# ethernet.net
KiCad netlist of a schematic drawn in Altium Designer
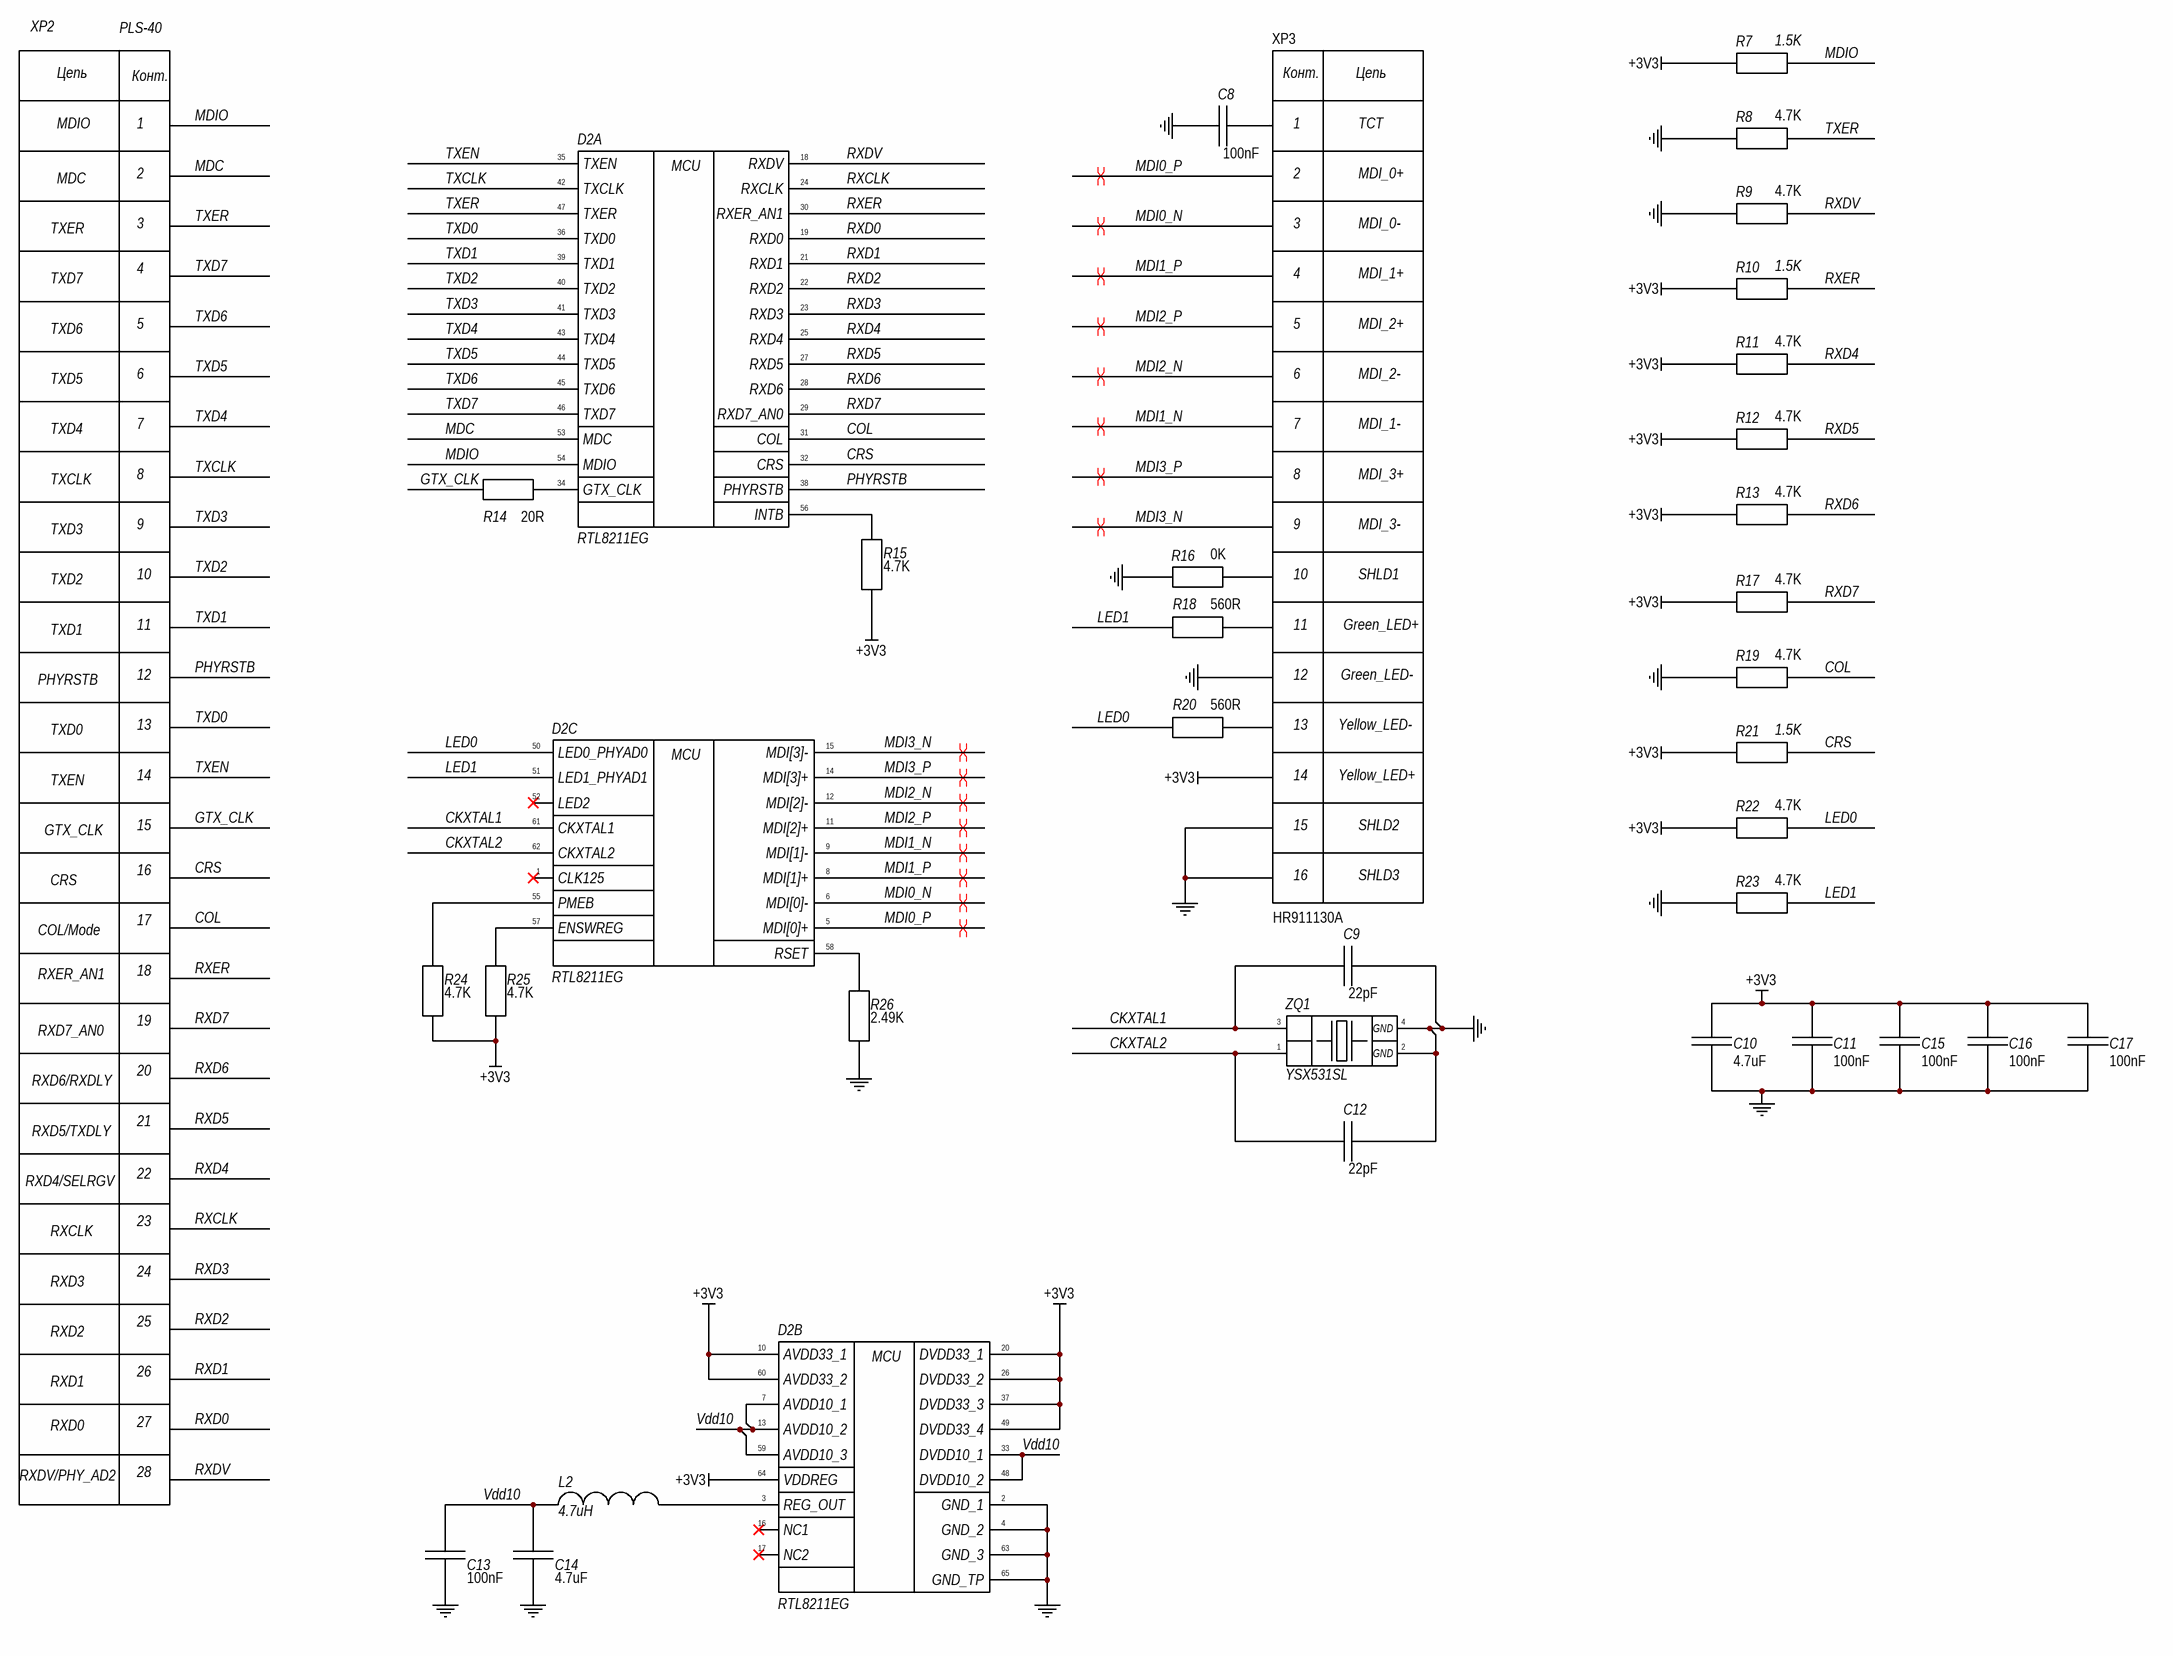
[diagram p0: ethernet.SchDoc]

(export (version "E")
  (design (tool "Eeschema 10.0.6"))
  (components
    (comp (ref "C8")
      (value "100nF")
      (footprint "SMD 0805")
      (description "Конденсатор номиналом 1.5 nF")
      (libsource (lib "Capacitors") (part "100nF"))
    )
    (comp (ref "C9")
      (value "22pF")
      (footprint "SMD 0805")
      (description "Конденсатор номиналом 22 pF")
      (libsource (lib "Capacitors") (part "22pF"))
    )
    (comp (ref "C10")
      (value "4.7uF")
      (footprint "SMD 0805")
      (description "Конденсатор номиналом 4.7 uF")
      (libsource (lib "Capacitors") (part "4.7uF"))
    )
    (comp (ref "C11")
      (value "100nF")
      (footprint "SMD 0805")
      (description "Конденсатор номиналом 1.5 nF")
      (libsource (lib "Capacitors") (part "100nF"))
    )
    (comp (ref "C12")
      (value "22pF")
      (footprint "SMD 0805")
      (description "Конденсатор номиналом 22 pF")
      (libsource (lib "Capacitors") (part "22pF"))
    )
    (comp (ref "C13")
      (value "100nF")
      (footprint "SMD 0805")
      (description "Конденсатор номиналом 1.5 nF")
      (libsource (lib "Capacitors") (part "100nF"))
    )
    (comp (ref "C14")
      (value "4.7uF")
      (footprint "SMD 0805")
      (description "Конденсатор номиналом 4.7 uF")
      (libsource (lib "Capacitors") (part "4.7uF"))
    )
    (comp (ref "C15")
      (value "100nF")
      (footprint "SMD 0805")
      (description "Конденсатор номиналом 1.5 nF")
      (libsource (lib "Capacitors") (part "100nF"))
    )
    (comp (ref "C16")
      (value "100nF")
      (footprint "SMD 0805")
      (description "Конденсатор номиналом 1.5 nF")
      (libsource (lib "Capacitors") (part "100nF"))
    )
    (comp (ref "C17")
      (value "100nF")
      (footprint "SMD 0805")
      (description "Конденсатор номиналом 1.5 nF")
      (libsource (lib "Capacitors") (part "100nF"))
    )
    (comp (ref "D2")
      (value "RTL8211EG")
      (footprint "Logic:QFN50P900X900X100_HS-65N")
      (libsource (lib "Logic") (part "RTL8211EG"))
    )
    (comp (ref "L2")
      (value "4.7uH")
      (footprint "SP43-4R7M")
      (description "Катушка индуктивности 4.7 мкГн")
      (libsource (lib "Inductors & Transformers") (part "4.7u"))
    )
    (comp (ref "R7")
      (value "1.5K")
      (footprint "RESC0805")
      (description "Резистор номиналом 1.5 кОм")
      (libsource (lib "Resistors") (part "1.5K"))
    )
    (comp (ref "R8")
      (value "4.7K")
      (footprint "RESC0805")
      (description "Резистор номиналом 4.7 кОм")
      (libsource (lib "Resistors") (part "4.7K"))
    )
    (comp (ref "R9")
      (value "4.7K")
      (footprint "RESC0805")
      (description "Резистор номиналом 4.7 кОм")
      (libsource (lib "Resistors") (part "4.7K"))
    )
    (comp (ref "R10")
      (value "1.5K")
      (footprint "RESC0805")
      (description "Резистор номиналом 1.5 кОм")
      (libsource (lib "Resistors") (part "1.5K"))
    )
    (comp (ref "R11")
      (value "4.7K")
      (footprint "RESC0805")
      (description "Резистор номиналом 4.7 кОм")
      (libsource (lib "Resistors") (part "4.7K"))
    )
    (comp (ref "R12")
      (value "4.7K")
      (footprint "RESC0805")
      (description "Резистор номиналом 4.7 кОм")
      (libsource (lib "Resistors") (part "4.7K"))
    )
    (comp (ref "R13")
      (value "4.7K")
      (footprint "RESC0805")
      (description "Резистор номиналом 4.7 кОм")
      (libsource (lib "Resistors") (part "4.7K"))
    )
    (comp (ref "R14")
      (value "20R")
      (footprint "RESC0805")
      (description "Резистор номиналом 20 Ом")
      (libsource (lib "Resistors") (part "20R"))
    )
    (comp (ref "R15")
      (value "4.7K")
      (footprint "RESC0805")
      (description "Резистор номиналом 4.7 кОм")
      (libsource (lib "Resistors") (part "4.7K"))
    )
    (comp (ref "R16")
      (value "0K")
      (footprint "RESC0805")
      (description "Резистор номиналом 0 Ом")
      (libsource (lib "Resistors") (part "0K"))
    )
    (comp (ref "R17")
      (value "4.7K")
      (footprint "RESC0805")
      (description "Резистор номиналом 4.7 кОм")
      (libsource (lib "Resistors") (part "4.7K"))
    )
    (comp (ref "R18")
      (value "560R")
      (footprint "RESC0805")
      (description "Резистор номиналом 560 Ом")
      (libsource (lib "Resistors") (part "560R"))
    )
    (comp (ref "R19")
      (value "4.7K")
      (footprint "RESC0805")
      (description "Резистор номиналом 4.7 кОм")
      (libsource (lib "Resistors") (part "4.7K"))
    )
    (comp (ref "R20")
      (value "560R")
      (footprint "RESC0805")
      (description "Резистор номиналом 560 Ом")
      (libsource (lib "Resistors") (part "560R"))
    )
    (comp (ref "R21")
      (value "1.5K")
      (footprint "RESC0805")
      (description "Резистор номиналом 1.5 кОм")
      (libsource (lib "Resistors") (part "1.5K"))
    )
    (comp (ref "R22")
      (value "4.7K")
      (footprint "RESC0805")
      (description "Резистор номиналом 4.7 кОм")
      (libsource (lib "Resistors") (part "4.7K"))
    )
    (comp (ref "R23")
      (value "4.7K")
      (footprint "RESC0805")
      (description "Резистор номиналом 4.7 кОм")
      (libsource (lib "Resistors") (part "4.7K"))
    )
    (comp (ref "R24")
      (value "4.7K")
      (footprint "RESC0805")
      (description "Резистор номиналом 4.7 кОм")
      (libsource (lib "Resistors") (part "4.7K"))
    )
    (comp (ref "R25")
      (value "4.7K")
      (footprint "RESC0805")
      (description "Резистор номиналом 4.7 кОм")
      (libsource (lib "Resistors") (part "4.7K"))
    )
    (comp (ref "R26")
      (value "2.49K")
      (footprint "RESC0805")
      (description "Резистор номиналом 2.49 кОм")
      (libsource (lib "Resistors") (part "2.49K"))
    )
    (comp (ref "XP2")
      (value "PLS-40")
      (footprint "PBD-28")
      (description "Служит для подключения разрабатываемой платы")
      (libsource (lib "Connectors") (part "SMT_FPGA"))
    )
    (comp (ref "XP3")
      (value "HR911130A")
      (footprint "Connectors:HR911130A")
      (description "Разъём RJ45 с встроенными трансформаторами и индикацией, 10/100Base-T Ethernet (HR911130A)")
      (libsource (lib "Connectors") (part "RJ-45"))
    )
    (comp (ref "ZQ1")
      (value "YSX531SL")
      (footprint "YSX531SL")
      (description "Кварцевый резонатор")
      (libsource (lib "Crystals & Oscillators") (part "YSX531SL"))
    )
  )
  (nets
    (net (code "1") (name "+3V3") (class "Default")
      (node (ref "C10") (pin "2") (pinfunction "2_2") (pintype "passive"))
      (node (ref "C11") (pin "2") (pinfunction "2_2") (pintype "passive"))
      (node (ref "C15") (pin "2") (pinfunction "2_2") (pintype "passive"))
      (node (ref "C16") (pin "2") (pinfunction "2_2") (pintype "passive"))
      (node (ref "C17") (pin "2") (pinfunction "2_2") (pintype "passive"))
      (node (ref "D2") (pin "10") (pinfunction "AVDD33_1_10") (pintype "passive"))
      (node (ref "D2") (pin "20") (pinfunction "DVDD33_1_20") (pintype "passive"))
      (node (ref "D2") (pin "26") (pinfunction "DVDD33_2_26") (pintype "passive"))
      (node (ref "D2") (pin "37") (pinfunction "DVDD33_3_37") (pintype "passive"))
      (node (ref "D2") (pin "49") (pinfunction "DVDD33_4_49") (pintype "passive"))
      (node (ref "D2") (pin "60") (pinfunction "AVDD33_2_60") (pintype "passive"))
      (node (ref "D2") (pin "64") (pinfunction "VDDREG_64") (pintype "passive"))
      (node (ref "R10") (pin "1") (pinfunction "1_1") (pintype "passive"))
      (node (ref "R11") (pin "1") (pinfunction "1_1") (pintype "passive"))
      (node (ref "R12") (pin "1") (pinfunction "1_1") (pintype "passive"))
      (node (ref "R13") (pin "1") (pinfunction "1_1") (pintype "passive"))
      (node (ref "R15") (pin "1") (pinfunction "1_1") (pintype "passive"))
      (node (ref "R17") (pin "1") (pinfunction "1_1") (pintype "passive"))
      (node (ref "R21") (pin "1") (pinfunction "1_1") (pintype "passive"))
      (node (ref "R22") (pin "1") (pinfunction "1_1") (pintype "passive"))
      (node (ref "R24") (pin "1") (pinfunction "1_1") (pintype "passive"))
      (node (ref "R25") (pin "1") (pinfunction "1_1") (pintype "passive"))
      (node (ref "R7") (pin "1") (pinfunction "1_1") (pintype "passive"))
      (node (ref "XP3") (pin "14") (pinfunction "14_14") (pintype "passive"))
    )
    (net (code "2") (name "/CKXTAL1") (class "Default")
      (node (ref "C9") (pin "1") (pinfunction "1_1") (pintype "passive"))
      (node (ref "D2") (pin "61") (pinfunction "CKXTAL1_61") (pintype "passive"))
      (node (ref "ZQ1") (pin "3") (pinfunction "3_3") (pintype "passive"))
    )
    (net (code "3") (name "/CKXTAL2") (class "Default")
      (node (ref "C12") (pin "1") (pinfunction "1_1") (pintype "passive"))
      (node (ref "D2") (pin "62") (pinfunction "CKXTAL2_62") (pintype "passive"))
      (node (ref "ZQ1") (pin "1") (pinfunction "1_1") (pintype "passive"))
    )
    (net (code "4") (name "/COL") (class "Default")
      (node (ref "D2") (pin "31") (pinfunction "COL_31") (pintype "passive"))
      (node (ref "R19") (pin "2") (pinfunction "2_2") (pintype "passive"))
      (node (ref "XP2") (pin "17") (pinfunction "17_17") (pintype "passive"))
    )
    (net (code "5") (name "/CRS") (class "Default")
      (node (ref "D2") (pin "32") (pinfunction "CRS_32") (pintype "passive"))
      (node (ref "R21") (pin "2") (pinfunction "2_2") (pintype "passive"))
      (node (ref "XP2") (pin "16") (pinfunction "16_16") (pintype "passive"))
    )
    (net (code "6") (name "/GTX_CLK") (class "Default")
      (node (ref "R14") (pin "1") (pinfunction "1_1") (pintype "passive"))
      (node (ref "XP2") (pin "15") (pinfunction "15_15") (pintype "passive"))
    )
    (net (code "7") (name "/LED0") (class "Default")
      (node (ref "D2") (pin "50") (pinfunction "LED0_PHYAD0_50") (pintype "passive"))
      (node (ref "R20") (pin "1") (pinfunction "1_1") (pintype "passive"))
      (node (ref "R22") (pin "2") (pinfunction "2_2") (pintype "passive"))
    )
    (net (code "8") (name "/LED1") (class "Default")
      (node (ref "D2") (pin "51") (pinfunction "LED1_PHYAD1_51") (pintype "passive"))
      (node (ref "R18") (pin "1") (pinfunction "1_1") (pintype "passive"))
      (node (ref "R23") (pin "2") (pinfunction "2_2") (pintype "passive"))
    )
    (net (code "9") (name "/MDC") (class "Default")
      (node (ref "D2") (pin "53") (pinfunction "MDC_53") (pintype "passive"))
      (node (ref "XP2") (pin "2") (pinfunction "2_2") (pintype "passive"))
    )
    (net (code "10") (name "/MDI0_N") (class "Default")
      (node (ref "D2") (pin "6") (pinfunction "MDI[0]-_6") (pintype "passive"))
      (node (ref "XP3") (pin "3") (pinfunction "3_3") (pintype "passive"))
    )
    (net (code "11") (name "/MDI0_P") (class "Default")
      (node (ref "D2") (pin "5") (pinfunction "MDI[0]+_5") (pintype "passive"))
      (node (ref "XP3") (pin "2") (pinfunction "2_2") (pintype "passive"))
    )
    (net (code "12") (name "/MDI1_N") (class "Default")
      (node (ref "D2") (pin "9") (pinfunction "MDI[1]-_9") (pintype "passive"))
      (node (ref "XP3") (pin "7") (pinfunction "7_7") (pintype "passive"))
    )
    (net (code "13") (name "/MDI1_P") (class "Default")
      (node (ref "D2") (pin "8") (pinfunction "MDI[1]+_8") (pintype "passive"))
      (node (ref "XP3") (pin "4") (pinfunction "4_4") (pintype "passive"))
    )
    (net (code "14") (name "/MDI2_N") (class "Default")
      (node (ref "D2") (pin "12") (pinfunction "MDI[2]-_12") (pintype "passive"))
      (node (ref "XP3") (pin "6") (pinfunction "6_6") (pintype "passive"))
    )
    (net (code "15") (name "/MDI2_P") (class "Default")
      (node (ref "D2") (pin "11") (pinfunction "MDI[2]+_11") (pintype "passive"))
      (node (ref "XP3") (pin "5") (pinfunction "5_5") (pintype "passive"))
    )
    (net (code "16") (name "/MDI3_N") (class "Default")
      (node (ref "D2") (pin "15") (pinfunction "MDI[3]-_15") (pintype "passive"))
      (node (ref "XP3") (pin "9") (pinfunction "9_9") (pintype "passive"))
    )
    (net (code "17") (name "/MDI3_P") (class "Default")
      (node (ref "D2") (pin "14") (pinfunction "MDI[3]+_14") (pintype "passive"))
      (node (ref "XP3") (pin "8") (pinfunction "8_8") (pintype "passive"))
    )
    (net (code "18") (name "/MDIO") (class "Default")
      (node (ref "D2") (pin "54") (pinfunction "MDIO_54") (pintype "passive"))
      (node (ref "R7") (pin "2") (pinfunction "2_2") (pintype "passive"))
      (node (ref "XP2") (pin "1") (pinfunction "1_1") (pintype "passive"))
    )
    (net (code "19") (name "/PHYRSTB") (class "Default")
      (node (ref "D2") (pin "38") (pinfunction "PHYRSTB_38") (pintype "passive"))
      (node (ref "XP2") (pin "12") (pinfunction "12_12") (pintype "passive"))
    )
    (net (code "20") (name "/RXCLK") (class "Default")
      (node (ref "D2") (pin "24") (pinfunction "RXCLK_24") (pintype "passive"))
      (node (ref "XP2") (pin "23") (pinfunction "23_23") (pintype "passive"))
    )
    (net (code "21") (name "/RXD0") (class "Default")
      (node (ref "D2") (pin "19") (pinfunction "RXD0_19") (pintype "passive"))
      (node (ref "XP2") (pin "27") (pinfunction "27_27") (pintype "passive"))
    )
    (net (code "22") (name "/RXD1") (class "Default")
      (node (ref "D2") (pin "21") (pinfunction "RXD1_21") (pintype "passive"))
      (node (ref "XP2") (pin "26") (pinfunction "26_26") (pintype "passive"))
    )
    (net (code "23") (name "/RXD2") (class "Default")
      (node (ref "D2") (pin "22") (pinfunction "RXD2_22") (pintype "passive"))
      (node (ref "XP2") (pin "25") (pinfunction "25_25") (pintype "passive"))
    )
    (net (code "24") (name "/RXD3") (class "Default")
      (node (ref "D2") (pin "23") (pinfunction "RXD3_23") (pintype "passive"))
      (node (ref "XP2") (pin "24") (pinfunction "24_24") (pintype "passive"))
    )
    (net (code "25") (name "/RXD4") (class "Default")
      (node (ref "D2") (pin "25") (pinfunction "RXD4_25") (pintype "passive"))
      (node (ref "R11") (pin "2") (pinfunction "2_2") (pintype "passive"))
      (node (ref "XP2") (pin "22") (pinfunction "22_22") (pintype "passive"))
    )
    (net (code "26") (name "/RXD5") (class "Default")
      (node (ref "D2") (pin "27") (pinfunction "RXD5_27") (pintype "passive"))
      (node (ref "R12") (pin "2") (pinfunction "2_2") (pintype "passive"))
      (node (ref "XP2") (pin "21") (pinfunction "21_21") (pintype "passive"))
    )
    (net (code "27") (name "/RXD6") (class "Default")
      (node (ref "D2") (pin "28") (pinfunction "RXD6_28") (pintype "passive"))
      (node (ref "R13") (pin "2") (pinfunction "2_2") (pintype "passive"))
      (node (ref "XP2") (pin "20") (pinfunction "20_20") (pintype "passive"))
    )
    (net (code "28") (name "/RXD7") (class "Default")
      (node (ref "D2") (pin "29") (pinfunction "RXD7_AN0_29") (pintype "passive"))
      (node (ref "R17") (pin "2") (pinfunction "2_2") (pintype "passive"))
      (node (ref "XP2") (pin "19") (pinfunction "19_19") (pintype "passive"))
    )
    (net (code "29") (name "/RXDV") (class "Default")
      (node (ref "D2") (pin "18") (pinfunction "RXDV_18") (pintype "passive"))
      (node (ref "R9") (pin "2") (pinfunction "2_2") (pintype "passive"))
      (node (ref "XP2") (pin "28") (pinfunction "28_28") (pintype "passive"))
    )
    (net (code "30") (name "/RXER") (class "Default")
      (node (ref "D2") (pin "30") (pinfunction "RXER_AN1_30") (pintype "passive"))
      (node (ref "R10") (pin "2") (pinfunction "2_2") (pintype "passive"))
      (node (ref "XP2") (pin "18") (pinfunction "18_18") (pintype "passive"))
    )
    (net (code "31") (name "/TXCLK") (class "Default")
      (node (ref "D2") (pin "42") (pinfunction "TXCLK_42") (pintype "passive"))
      (node (ref "XP2") (pin "8") (pinfunction "8_8") (pintype "passive"))
    )
    (net (code "32") (name "/TXD0") (class "Default")
      (node (ref "D2") (pin "36") (pinfunction "TXD0_36") (pintype "passive"))
      (node (ref "XP2") (pin "13") (pinfunction "13_13") (pintype "passive"))
    )
    (net (code "33") (name "/TXD1") (class "Default")
      (node (ref "D2") (pin "39") (pinfunction "TXD1_39") (pintype "passive"))
      (node (ref "XP2") (pin "11") (pinfunction "11_11") (pintype "passive"))
    )
    (net (code "34") (name "/TXD2") (class "Default")
      (node (ref "D2") (pin "40") (pinfunction "TXD2_40") (pintype "passive"))
      (node (ref "XP2") (pin "10") (pinfunction "10_10") (pintype "passive"))
    )
    (net (code "35") (name "/TXD3") (class "Default")
      (node (ref "D2") (pin "41") (pinfunction "TXD3_41") (pintype "passive"))
      (node (ref "XP2") (pin "9") (pinfunction "9_9") (pintype "passive"))
    )
    (net (code "36") (name "/TXD4") (class "Default")
      (node (ref "D2") (pin "43") (pinfunction "TXD4_43") (pintype "passive"))
      (node (ref "XP2") (pin "7") (pinfunction "7_7") (pintype "passive"))
    )
    (net (code "37") (name "/TXD5") (class "Default")
      (node (ref "D2") (pin "44") (pinfunction "TXD5_44") (pintype "passive"))
      (node (ref "XP2") (pin "6") (pinfunction "6_6") (pintype "passive"))
    )
    (net (code "38") (name "/TXD6") (class "Default")
      (node (ref "D2") (pin "45") (pinfunction "TXD6_45") (pintype "passive"))
      (node (ref "XP2") (pin "5") (pinfunction "5_5") (pintype "passive"))
    )
    (net (code "39") (name "/TXD7") (class "Default")
      (node (ref "D2") (pin "46") (pinfunction "TXD7_46") (pintype "passive"))
      (node (ref "XP2") (pin "4") (pinfunction "4_4") (pintype "passive"))
    )
    (net (code "40") (name "/TXEN") (class "Default")
      (node (ref "D2") (pin "35") (pinfunction "TXEN_35") (pintype "passive"))
      (node (ref "XP2") (pin "14") (pinfunction "14_14") (pintype "passive"))
    )
    (net (code "41") (name "/TXER") (class "Default")
      (node (ref "D2") (pin "47") (pinfunction "TXER_47") (pintype "passive"))
      (node (ref "R8") (pin "2") (pinfunction "2_2") (pintype "passive"))
      (node (ref "XP2") (pin "3") (pinfunction "3_3") (pintype "passive"))
    )
    (net (code "42") (name "/Vdd10") (class "Default")
      (node (ref "C13") (pin "2") (pinfunction "2_2") (pintype "passive"))
      (node (ref "C14") (pin "2") (pinfunction "2_2") (pintype "passive"))
      (node (ref "D2") (pin "13") (pinfunction "AVDD10_2_13") (pintype "passive"))
      (node (ref "D2") (pin "33") (pinfunction "DVDD10_1_33") (pintype "passive"))
      (node (ref "D2") (pin "48") (pinfunction "DVDD10_2_48") (pintype "passive"))
      (node (ref "D2") (pin "59") (pinfunction "AVDD10_3_59") (pintype "passive"))
      (node (ref "D2") (pin "7") (pinfunction "AVDD10_1_7") (pintype "passive"))
      (node (ref "L2") (pin "1") (pinfunction "1_1") (pintype "passive"))
    )
    (net (code "43") (name "GND") (class "Default")
      (node (ref "C10") (pin "1") (pinfunction "1_1") (pintype "passive"))
      (node (ref "C11") (pin "1") (pinfunction "1_1") (pintype "passive"))
      (node (ref "C12") (pin "2") (pinfunction "2_2") (pintype "passive"))
      (node (ref "C13") (pin "1") (pinfunction "1_1") (pintype "passive"))
      (node (ref "C14") (pin "1") (pinfunction "1_1") (pintype "passive"))
      (node (ref "C15") (pin "1") (pinfunction "1_1") (pintype "passive"))
      (node (ref "C16") (pin "1") (pinfunction "1_1") (pintype "passive"))
      (node (ref "C17") (pin "1") (pinfunction "1_1") (pintype "passive"))
      (node (ref "C8") (pin "1") (pinfunction "1_1") (pintype "passive"))
      (node (ref "C9") (pin "2") (pinfunction "2_2") (pintype "passive"))
      (node (ref "D2") (pin "2") (pinfunction "GND_1_2") (pintype "passive"))
      (node (ref "D2") (pin "4") (pinfunction "GND_2_4") (pintype "passive"))
      (node (ref "D2") (pin "63") (pinfunction "GND_3_63") (pintype "passive"))
      (node (ref "D2") (pin "65") (pinfunction "GND_TP_65") (pintype "passive"))
      (node (ref "R16") (pin "1") (pinfunction "1_1") (pintype "passive"))
      (node (ref "R19") (pin "1") (pinfunction "1_1") (pintype "passive"))
      (node (ref "R23") (pin "1") (pinfunction "1_1") (pintype "passive"))
      (node (ref "R26") (pin "1") (pinfunction "1_1") (pintype "passive"))
      (node (ref "R8") (pin "1") (pinfunction "1_1") (pintype "passive"))
      (node (ref "R9") (pin "1") (pinfunction "1_1") (pintype "passive"))
      (node (ref "XP3") (pin "12") (pinfunction "12_12") (pintype "passive"))
      (node (ref "XP3") (pin "15") (pinfunction "15_15") (pintype "passive"))
      (node (ref "XP3") (pin "16") (pinfunction "16_16") (pintype "passive"))
      (node (ref "ZQ1") (pin "2") (pinfunction "GND_2") (pintype "passive"))
      (node (ref "ZQ1") (pin "4") (pinfunction "GND_4") (pintype "passive"))
    )
    (net (code "44") (name "Net-(C8-Pad2)") (class "Default")
      (node (ref "C8") (pin "2") (pinfunction "2_2") (pintype "passive"))
      (node (ref "XP3") (pin "1") (pinfunction "1_1") (pintype "passive"))
    )
    (net (code "45") (name "Net-(D2A-GTX_CLK)") (class "Default")
      (node (ref "D2") (pin "34") (pinfunction "GTX_CLK_34") (pintype "passive"))
      (node (ref "R14") (pin "2") (pinfunction "2_2") (pintype "passive"))
    )
    (net (code "46") (name "Net-(D2A-INTB)") (class "Default")
      (node (ref "D2") (pin "56") (pinfunction "INTB_56") (pintype "passive"))
      (node (ref "R15") (pin "2") (pinfunction "2_2") (pintype "passive"))
    )
    (net (code "47") (name "Net-(D2B-REG_OUT)") (class "Default")
      (node (ref "D2") (pin "3") (pinfunction "REG_OUT_3") (pintype "passive"))
      (node (ref "L2") (pin "2") (pinfunction "2_2") (pintype "passive"))
    )
    (net (code "48") (name "Net-(D2C-ENSWREG)") (class "Default")
      (node (ref "D2") (pin "57") (pinfunction "ENSWREG_57") (pintype "passive"))
      (node (ref "R25") (pin "2") (pinfunction "2_2") (pintype "passive"))
    )
    (net (code "49") (name "Net-(D2C-PMEB)") (class "Default")
      (node (ref "D2") (pin "55") (pinfunction "PMEB_55") (pintype "passive"))
      (node (ref "R24") (pin "2") (pinfunction "2_2") (pintype "passive"))
    )
    (net (code "50") (name "Net-(D2C-RSET)") (class "Default")
      (node (ref "D2") (pin "58") (pinfunction "RSET_58") (pintype "passive"))
      (node (ref "R26") (pin "2") (pinfunction "2_2") (pintype "passive"))
    )
    (net (code "51") (name "Net-(R16-Pad2)") (class "Default")
      (node (ref "R16") (pin "2") (pinfunction "2_2") (pintype "passive"))
      (node (ref "XP3") (pin "10") (pinfunction "10_10") (pintype "passive"))
    )
    (net (code "52") (name "Net-(R18-Pad2)") (class "Default")
      (node (ref "R18") (pin "2") (pinfunction "2_2") (pintype "passive"))
      (node (ref "XP3") (pin "11") (pinfunction "11_11") (pintype "passive"))
    )
    (net (code "53") (name "Net-(R20-Pad2)") (class "Default")
      (node (ref "R20") (pin "2") (pinfunction "2_2") (pintype "passive"))
      (node (ref "XP3") (pin "13") (pinfunction "13_13") (pintype "passive"))
    )
    (net (code "54") (name "unconnected-(D2B-NC1-Pad16)") (class "Default")
      (node (ref "D2") (pin "16") (pinfunction "NC1_16") (pintype "passive+no_connect"))
    )
    (net (code "55") (name "unconnected-(D2B-NC2-Pad17)") (class "Default")
      (node (ref "D2") (pin "17") (pinfunction "NC2_17") (pintype "passive+no_connect"))
    )
    (net (code "56") (name "unconnected-(D2C-CLK125-Pad1)") (class "Default")
      (node (ref "D2") (pin "1") (pinfunction "CLK125_1") (pintype "passive+no_connect"))
    )
    (net (code "57") (name "unconnected-(D2C-LED2-Pad52)") (class "Default")
      (node (ref "D2") (pin "52") (pinfunction "LED2_52") (pintype "passive+no_connect"))
    )
  )
)
